# yamato.net
KiCad netlist of a schematic drawn in EAGLE
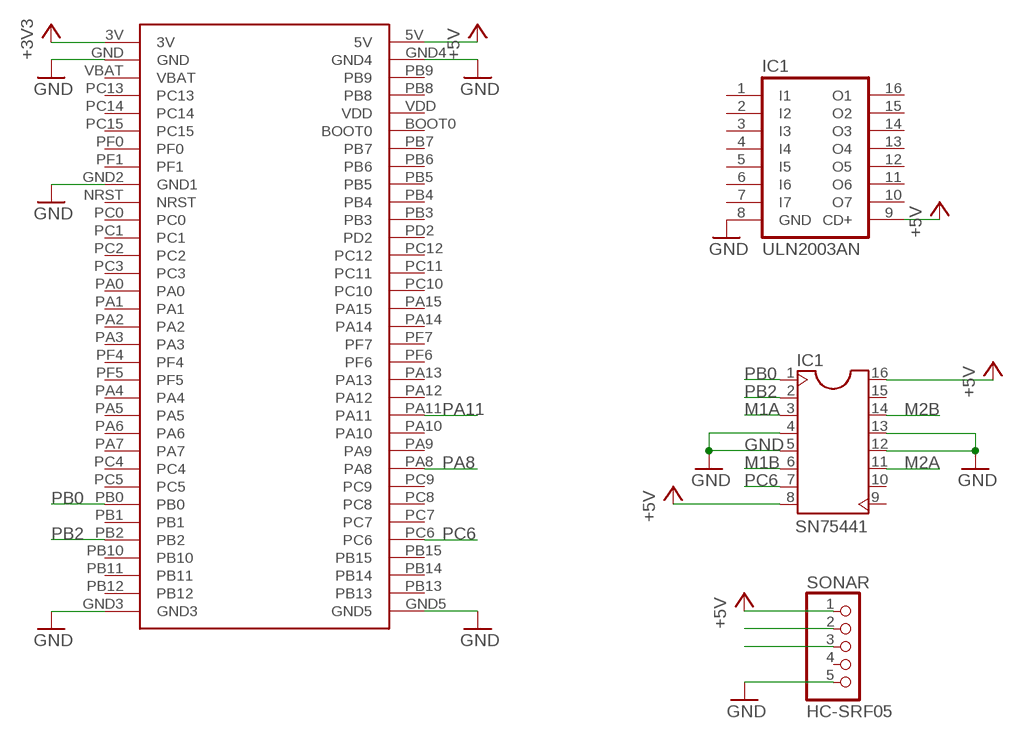
[diagram p0: schematic, sheet 1]

(export (version "E")
  (design (tool "Eeschema 10.0.6"))
  (components
    (comp (ref "IC1")
      (value "ULN2003AN")
      (footprint "eagle-import:DIL16")
      (libsource (lib "eagle-import") (part "ULN2003AN"))
    )
    (comp (ref "SONAR")
      (value "HC-SRF05")
      (footprint "eagle-import:1X05")
      (libsource (lib "eagle-import") (part "PINHD-1X5"))
    )
    (comp (ref "U$1")
      (value "STM32F0DISCOVERY-DEVICE")
      (footprint "eagle-import:STM32F0DISCOVERY-PACKAGE")
      (libsource (lib "eagle-import") (part "STM32F0DISCOVERY-DEVICE"))
    )
    (comp (ref "U$2")
      (value "SN75441-DEVICESN75411-SOCKET")
      (footprint "eagle-import:SOCKET-16")
      (libsource (lib "eagle-import") (part "SN75441-DEVICESN75411-SOCKET"))
    )
  )
  (nets
    (net (code "1") (name "+3V3") (class "Default")
      (node (ref "U$1") (pin "3V") (pinfunction "3V_3V") (pintype "bidirectional"))
    )
    (net (code "2") (name "+5V") (class "Default")
      (node (ref "IC1") (pin "9") (pinfunction "CD+_9") (pintype "passive"))
      (node (ref "SONAR") (pin "1") (pinfunction "1_1") (pintype "passive"))
      (node (ref "U$1") (pin "5V") (pinfunction "5V_5V") (pintype "bidirectional"))
      (node (ref "U$2") (pin "16") (pinfunction "VCC1_16") (pintype "power_in"))
      (node (ref "U$2") (pin "8") (pinfunction "VCC2_8") (pintype "power_in"))
    )
    (net (code "3") (name "/M1A") (class "Default")
      (node (ref "U$2") (pin "3") (pinfunction "1Y_3") (pintype "output"))
    )
    (net (code "4") (name "/M1B") (class "Default")
      (node (ref "U$2") (pin "6") (pinfunction "2Y_6") (pintype "output"))
    )
    (net (code "5") (name "/M2A") (class "Default")
      (node (ref "U$2") (pin "11") (pinfunction "3Y_11") (pintype "output"))
    )
    (net (code "6") (name "/M2B") (class "Default")
      (node (ref "U$2") (pin "14") (pinfunction "4Y_14") (pintype "output"))
    )
    (net (code "7") (name "/PA8") (class "Default")
      (node (ref "SONAR") (pin "3") (pinfunction "3_3") (pintype "passive"))
      (node (ref "U$1") (pin "PA8") (pinfunction "PA8_PA8") (pintype "bidirectional"))
    )
    (net (code "8") (name "/PA11") (class "Default")
      (node (ref "SONAR") (pin "2") (pinfunction "2_2") (pintype "passive"))
      (node (ref "U$1") (pin "PA11") (pinfunction "PA11_PA11") (pintype "bidirectional"))
    )
    (net (code "9") (name "/PB0") (class "Default")
      (node (ref "U$1") (pin "PB0") (pinfunction "PB0_PB0") (pintype "bidirectional"))
      (node (ref "U$2") (pin "1") (pinfunction "12EN_1") (pintype "input"))
    )
    (net (code "10") (name "/PB2") (class "Default")
      (node (ref "U$1") (pin "PB2") (pinfunction "PB2_PB2") (pintype "bidirectional"))
      (node (ref "U$2") (pin "2") (pinfunction "1A_2") (pintype "input"))
    )
    (net (code "11") (name "/PC6") (class "Default")
      (node (ref "U$1") (pin "PC6") (pinfunction "PC6_PC6") (pintype "bidirectional"))
      (node (ref "U$2") (pin "7") (pinfunction "2A_7") (pintype "input"))
    )
    (net (code "12") (name "GND") (class "Default")
      (node (ref "IC1") (pin "8") (pinfunction "GND_8") (pintype "power_in"))
      (node (ref "SONAR") (pin "5") (pinfunction "5_5") (pintype "passive"))
      (node (ref "U$1") (pin "GND") (pinfunction "GND_GND") (pintype "bidirectional"))
      (node (ref "U$1") (pin "GND2") (pinfunction "GND1_GND2") (pintype "bidirectional"))
      (node (ref "U$1") (pin "GND3") (pinfunction "GND3_GND3") (pintype "bidirectional"))
      (node (ref "U$1") (pin "GND4") (pinfunction "GND4_GND4") (pintype "bidirectional"))
      (node (ref "U$1") (pin "GND5") (pinfunction "GND5_GND5") (pintype "bidirectional"))
      (node (ref "U$2") (pin "12") (pinfunction "GND2_12") (pintype "power_in"))
      (node (ref "U$2") (pin "13") (pinfunction "GND3_13") (pintype "power_in"))
      (node (ref "U$2") (pin "4") (pinfunction "GND_4") (pintype "power_in"))
      (node (ref "U$2") (pin "5") (pinfunction "GND1_5") (pintype "power_in"))
    )
    (net (code "13") (name "unconnected-(IC1-I1-Pad1)") (class "Default")
      (node (ref "IC1") (pin "1") (pinfunction "I1_1") (pintype "input"))
    )
    (net (code "14") (name "unconnected-(IC1-I2-Pad2)") (class "Default")
      (node (ref "IC1") (pin "2") (pinfunction "I2_2") (pintype "input"))
    )
    (net (code "15") (name "unconnected-(IC1-I3-Pad3)") (class "Default")
      (node (ref "IC1") (pin "3") (pinfunction "I3_3") (pintype "input"))
    )
    (net (code "16") (name "unconnected-(IC1-I4-Pad4)") (class "Default")
      (node (ref "IC1") (pin "4") (pinfunction "I4_4") (pintype "input"))
    )
    (net (code "17") (name "unconnected-(IC1-I5-Pad5)") (class "Default")
      (node (ref "IC1") (pin "5") (pinfunction "I5_5") (pintype "input"))
    )
    (net (code "18") (name "unconnected-(IC1-I6-Pad6)") (class "Default")
      (node (ref "IC1") (pin "6") (pinfunction "I6_6") (pintype "input"))
    )
    (net (code "19") (name "unconnected-(IC1-I7-Pad7)") (class "Default")
      (node (ref "IC1") (pin "7") (pinfunction "I7_7") (pintype "input"))
    )
    (net (code "20") (name "unconnected-(IC1-O1-Pad16)") (class "Default")
      (node (ref "IC1") (pin "16") (pinfunction "O1_16") (pintype "open_collector"))
    )
    (net (code "21") (name "unconnected-(IC1-O2-Pad15)") (class "Default")
      (node (ref "IC1") (pin "15") (pinfunction "O2_15") (pintype "open_collector"))
    )
    (net (code "22") (name "unconnected-(IC1-O3-Pad14)") (class "Default")
      (node (ref "IC1") (pin "14") (pinfunction "O3_14") (pintype "open_collector"))
    )
    (net (code "23") (name "unconnected-(IC1-O4-Pad13)") (class "Default")
      (node (ref "IC1") (pin "13") (pinfunction "O4_13") (pintype "open_collector"))
    )
    (net (code "24") (name "unconnected-(IC1-O5-Pad12)") (class "Default")
      (node (ref "IC1") (pin "12") (pinfunction "O5_12") (pintype "open_collector"))
    )
    (net (code "25") (name "unconnected-(IC1-O6-Pad11)") (class "Default")
      (node (ref "IC1") (pin "11") (pinfunction "O6_11") (pintype "open_collector"))
    )
    (net (code "26") (name "unconnected-(IC1-O7-Pad10)") (class "Default")
      (node (ref "IC1") (pin "10") (pinfunction "O7_10") (pintype "open_collector"))
    )
    (net (code "27") (name "unconnected-(SONAR-Pad4)") (class "Default")
      (node (ref "SONAR") (pin "4") (pinfunction "4_4") (pintype "passive"))
    )
    (net (code "28") (name "unconnected-(U$1-PadBOOT0)") (class "Default")
      (node (ref "U$1") (pin "BOOT0") (pinfunction "BOOT0_BOOT0") (pintype "bidirectional"))
    )
    (net (code "29") (name "unconnected-(U$1-PadNRST)") (class "Default")
      (node (ref "U$1") (pin "NRST") (pinfunction "NRST_NRST") (pintype "bidirectional"))
    )
    (net (code "30") (name "unconnected-(U$1-PadPA0)") (class "Default")
      (node (ref "U$1") (pin "PA0") (pinfunction "PA0_PA0") (pintype "bidirectional"))
    )
    (net (code "31") (name "unconnected-(U$1-PadPA1)") (class "Default")
      (node (ref "U$1") (pin "PA1") (pinfunction "PA1_PA1") (pintype "bidirectional"))
    )
    (net (code "32") (name "unconnected-(U$1-PadPA2)") (class "Default")
      (node (ref "U$1") (pin "PA2") (pinfunction "PA2_PA2") (pintype "bidirectional"))
    )
    (net (code "33") (name "unconnected-(U$1-PadPA3)") (class "Default")
      (node (ref "U$1") (pin "PA3") (pinfunction "PA3_PA3") (pintype "bidirectional"))
    )
    (net (code "34") (name "unconnected-(U$1-PadPA4)") (class "Default")
      (node (ref "U$1") (pin "PA4") (pinfunction "PA4_PA4") (pintype "bidirectional"))
    )
    (net (code "35") (name "unconnected-(U$1-PadPA5)") (class "Default")
      (node (ref "U$1") (pin "PA5") (pinfunction "PA5_PA5") (pintype "bidirectional"))
    )
    (net (code "36") (name "unconnected-(U$1-PadPA6)") (class "Default")
      (node (ref "U$1") (pin "PA6") (pinfunction "PA6_PA6") (pintype "bidirectional"))
    )
    (net (code "37") (name "unconnected-(U$1-PadPA7)") (class "Default")
      (node (ref "U$1") (pin "PA7") (pinfunction "PA7_PA7") (pintype "bidirectional"))
    )
    (net (code "38") (name "unconnected-(U$1-PadPA9)") (class "Default")
      (node (ref "U$1") (pin "PA9") (pinfunction "PA9_PA9") (pintype "bidirectional"))
    )
    (net (code "39") (name "unconnected-(U$1-PadPA10)") (class "Default")
      (node (ref "U$1") (pin "PA10") (pinfunction "PA10_PA10") (pintype "bidirectional"))
    )
    (net (code "40") (name "unconnected-(U$1-PadPA12)") (class "Default")
      (node (ref "U$1") (pin "PA12") (pinfunction "PA12_PA12") (pintype "bidirectional"))
    )
    (net (code "41") (name "unconnected-(U$1-PadPA13)") (class "Default")
      (node (ref "U$1") (pin "PA13") (pinfunction "PA13_PA13") (pintype "bidirectional"))
    )
    (net (code "42") (name "unconnected-(U$1-PadPA14)") (class "Default")
      (node (ref "U$1") (pin "PA14") (pinfunction "PA14_PA14") (pintype "bidirectional"))
    )
    (net (code "43") (name "unconnected-(U$1-PadPA15)") (class "Default")
      (node (ref "U$1") (pin "PA15") (pinfunction "PA15_PA15") (pintype "bidirectional"))
    )
    (net (code "44") (name "unconnected-(U$1-PadPB1)") (class "Default")
      (node (ref "U$1") (pin "PB1") (pinfunction "PB1_PB1") (pintype "bidirectional"))
    )
    (net (code "45") (name "unconnected-(U$1-PadPB3)") (class "Default")
      (node (ref "U$1") (pin "PB3") (pinfunction "PB3_PB3") (pintype "bidirectional"))
    )
    (net (code "46") (name "unconnected-(U$1-PadPB4)") (class "Default")
      (node (ref "U$1") (pin "PB4") (pinfunction "PB4_PB4") (pintype "bidirectional"))
    )
    (net (code "47") (name "unconnected-(U$1-PadPB5)") (class "Default")
      (node (ref "U$1") (pin "PB5") (pinfunction "PB5_PB5") (pintype "bidirectional"))
    )
    (net (code "48") (name "unconnected-(U$1-PadPB6)") (class "Default")
      (node (ref "U$1") (pin "PB6") (pinfunction "PB6_PB6") (pintype "bidirectional"))
    )
    (net (code "49") (name "unconnected-(U$1-PadPB7)") (class "Default")
      (node (ref "U$1") (pin "PB7") (pinfunction "PB7_PB7") (pintype "bidirectional"))
    )
    (net (code "50") (name "unconnected-(U$1-PadPB8)") (class "Default")
      (node (ref "U$1") (pin "PB8") (pinfunction "PB8_PB8") (pintype "bidirectional"))
    )
    (net (code "51") (name "unconnected-(U$1-PadPB9)") (class "Default")
      (node (ref "U$1") (pin "PB9") (pinfunction "PB9_PB9") (pintype "bidirectional"))
    )
    (net (code "52") (name "unconnected-(U$1-PadPB10)") (class "Default")
      (node (ref "U$1") (pin "PB10") (pinfunction "PB10_PB10") (pintype "bidirectional"))
    )
    (net (code "53") (name "unconnected-(U$1-PadPB11)") (class "Default")
      (node (ref "U$1") (pin "PB11") (pinfunction "PB11_PB11") (pintype "bidirectional"))
    )
    (net (code "54") (name "unconnected-(U$1-PadPB12)") (class "Default")
      (node (ref "U$1") (pin "PB12") (pinfunction "PB12_PB12") (pintype "bidirectional"))
    )
    (net (code "55") (name "unconnected-(U$1-PadPB13)") (class "Default")
      (node (ref "U$1") (pin "PB13") (pinfunction "PB13_PB13") (pintype "bidirectional"))
    )
    (net (code "56") (name "unconnected-(U$1-PadPB14)") (class "Default")
      (node (ref "U$1") (pin "PB14") (pinfunction "PB14_PB14") (pintype "bidirectional"))
    )
    (net (code "57") (name "unconnected-(U$1-PadPB15)") (class "Default")
      (node (ref "U$1") (pin "PB15") (pinfunction "PB15_PB15") (pintype "bidirectional"))
    )
    (net (code "58") (name "unconnected-(U$1-PadPC0)") (class "Default")
      (node (ref "U$1") (pin "PC0") (pinfunction "PC0_PC0") (pintype "bidirectional"))
    )
    (net (code "59") (name "unconnected-(U$1-PadPC1)") (class "Default")
      (node (ref "U$1") (pin "PC1") (pinfunction "PC1_PC1") (pintype "bidirectional"))
    )
    (net (code "60") (name "unconnected-(U$1-PadPC2)") (class "Default")
      (node (ref "U$1") (pin "PC2") (pinfunction "PC2_PC2") (pintype "bidirectional"))
    )
    (net (code "61") (name "unconnected-(U$1-PadPC3)") (class "Default")
      (node (ref "U$1") (pin "PC3") (pinfunction "PC3_PC3") (pintype "bidirectional"))
    )
    (net (code "62") (name "unconnected-(U$1-PadPC4)") (class "Default")
      (node (ref "U$1") (pin "PC4") (pinfunction "PC4_PC4") (pintype "bidirectional"))
    )
    (net (code "63") (name "unconnected-(U$1-PadPC5)") (class "Default")
      (node (ref "U$1") (pin "PC5") (pinfunction "PC5_PC5") (pintype "bidirectional"))
    )
    (net (code "64") (name "unconnected-(U$1-PadPC7)") (class "Default")
      (node (ref "U$1") (pin "PC7") (pinfunction "PC7_PC7") (pintype "bidirectional"))
    )
    (net (code "65") (name "unconnected-(U$1-PadPC8)") (class "Default")
      (node (ref "U$1") (pin "PC8") (pinfunction "PC8_PC8") (pintype "bidirectional"))
    )
    (net (code "66") (name "unconnected-(U$1-PadPC9)") (class "Default")
      (node (ref "U$1") (pin "PC9") (pinfunction "PC9_PC9") (pintype "bidirectional"))
    )
    (net (code "67") (name "unconnected-(U$1-PadPC10)") (class "Default")
      (node (ref "U$1") (pin "PC10") (pinfunction "PC10_PC10") (pintype "bidirectional"))
    )
    (net (code "68") (name "unconnected-(U$1-PadPC11)") (class "Default")
      (node (ref "U$1") (pin "PC11") (pinfunction "PC11_PC11") (pintype "bidirectional"))
    )
    (net (code "69") (name "unconnected-(U$1-PadPC12)") (class "Default")
      (node (ref "U$1") (pin "PC12") (pinfunction "PC12_PC12") (pintype "bidirectional"))
    )
    (net (code "70") (name "unconnected-(U$1-PadPC13)") (class "Default")
      (node (ref "U$1") (pin "PC13") (pinfunction "PC13_PC13") (pintype "bidirectional"))
    )
    (net (code "71") (name "unconnected-(U$1-PadPC14)") (class "Default")
      (node (ref "U$1") (pin "PC14") (pinfunction "PC14_PC14") (pintype "bidirectional"))
    )
    (net (code "72") (name "unconnected-(U$1-PadPC15)") (class "Default")
      (node (ref "U$1") (pin "PC15") (pinfunction "PC15_PC15") (pintype "bidirectional"))
    )
    (net (code "73") (name "unconnected-(U$1-PadPD2)") (class "Default")
      (node (ref "U$1") (pin "PD2") (pinfunction "PD2_PD2") (pintype "bidirectional"))
    )
    (net (code "74") (name "unconnected-(U$1-PadPF0)") (class "Default")
      (node (ref "U$1") (pin "PF0") (pinfunction "PF0_PF0") (pintype "bidirectional"))
    )
    (net (code "75") (name "unconnected-(U$1-PadPF1)") (class "Default")
      (node (ref "U$1") (pin "PF1") (pinfunction "PF1_PF1") (pintype "bidirectional"))
    )
    (net (code "76") (name "unconnected-(U$1-PadPF4)") (class "Default")
      (node (ref "U$1") (pin "PF4") (pinfunction "PF4_PF4") (pintype "bidirectional"))
    )
    (net (code "77") (name "unconnected-(U$1-PadPF5)") (class "Default")
      (node (ref "U$1") (pin "PF5") (pinfunction "PF5_PF5") (pintype "bidirectional"))
    )
    (net (code "78") (name "unconnected-(U$1-PadPF6)") (class "Default")
      (node (ref "U$1") (pin "PF6") (pinfunction "PF6_PF6") (pintype "bidirectional"))
    )
    (net (code "79") (name "unconnected-(U$1-PadPF7)") (class "Default")
      (node (ref "U$1") (pin "PF7") (pinfunction "PF7_PF7") (pintype "bidirectional"))
    )
    (net (code "80") (name "unconnected-(U$1-PadVBAT)") (class "Default")
      (node (ref "U$1") (pin "VBAT") (pinfunction "VBAT_VBAT") (pintype "bidirectional"))
    )
    (net (code "81") (name "unconnected-(U$1-PadVDD)") (class "Default")
      (node (ref "U$1") (pin "VDD") (pinfunction "VDD_VDD") (pintype "bidirectional"))
    )
    (net (code "82") (name "unconnected-(U$2-3A-Pad10)") (class "Default")
      (node (ref "U$2") (pin "10") (pinfunction "3A_10") (pintype "input"))
    )
    (net (code "83") (name "unconnected-(U$2-4A-Pad15)") (class "Default")
      (node (ref "U$2") (pin "15") (pinfunction "4A_15") (pintype "input"))
    )
    (net (code "84") (name "unconnected-(U$2-34EN-Pad9)") (class "Default")
      (node (ref "U$2") (pin "9") (pinfunction "34EN_9") (pintype "input"))
    )
  )
)
